# led3.net
KiCad netlist of a schematic drawn in Altium Designer
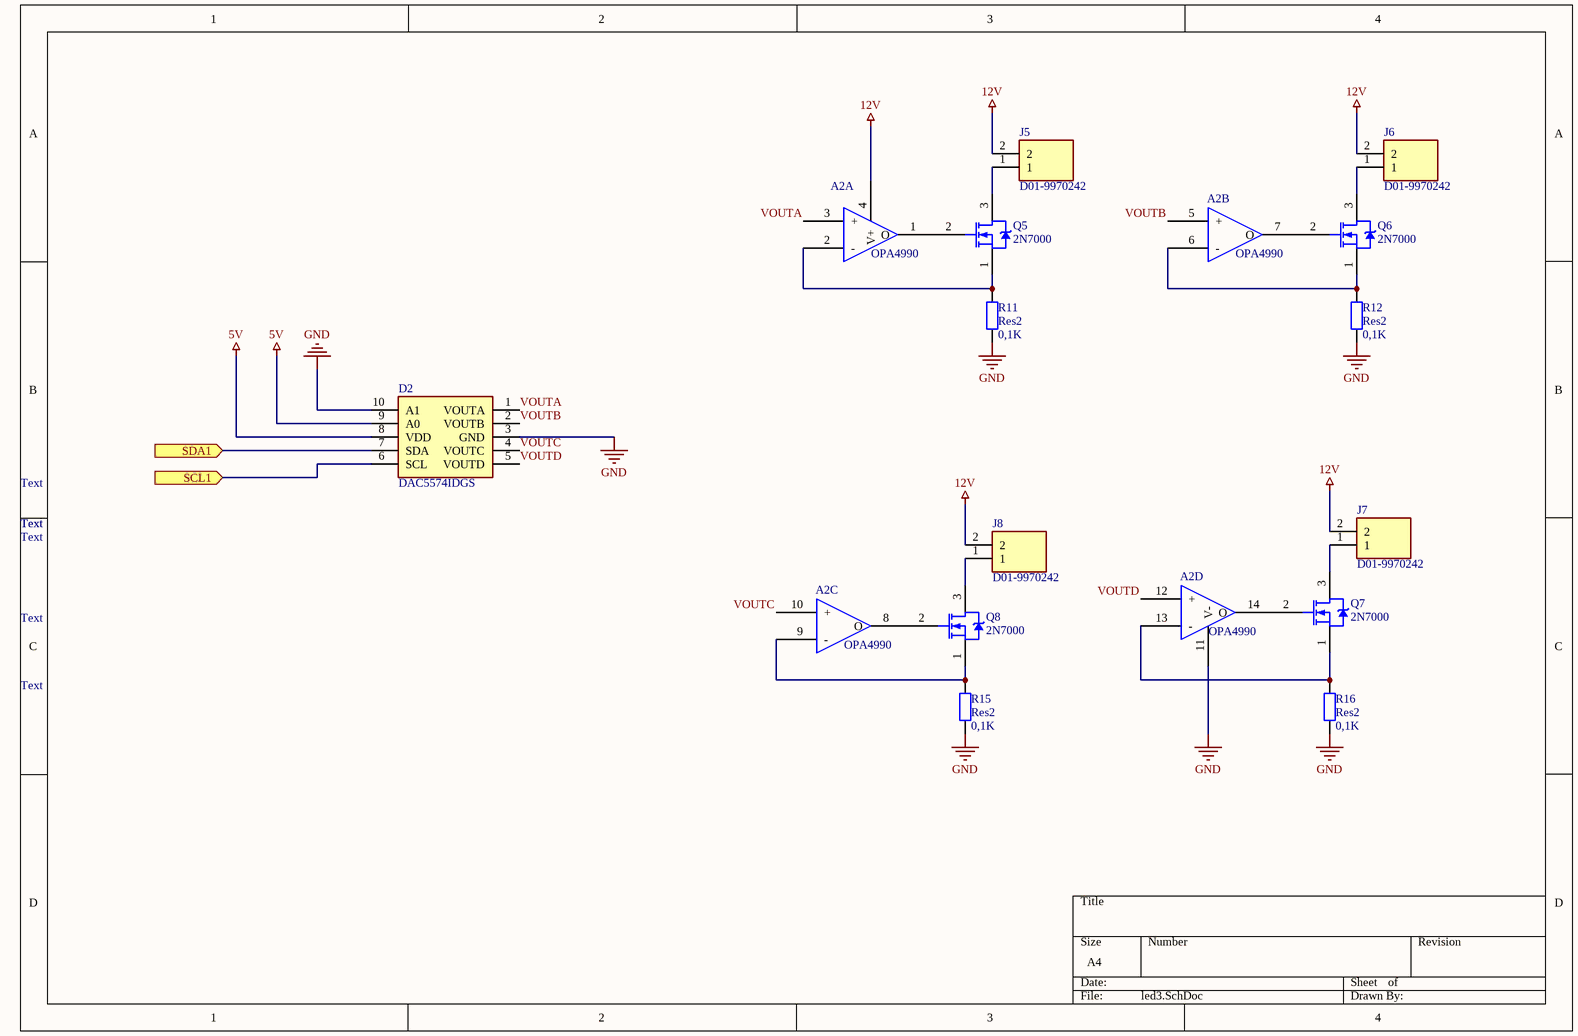
[diagram p0: led3.SchDoc]

(export (version "E")
  (design (tool "Eeschema 10.0.6"))
  (components
    (comp (ref "A2")
      (value "OPA4990")
      (footprint "SOIC127P600X175-14N")
      (libsource (lib "Kalibracija") (part "OPA4990"))
    )
    (comp (ref "D2")
      (value "DAC5574IDGS")
      (footprint "SOP50P490X110-10N")
      (description "Integrated Circuit")
      (fields
        (field (name "MOUSER PART NUMBER") "595-DAC5574IDGS")
        (field (name "RS PART NUMBER") "6621533P")
      )
      (libsource (lib "*") (part "DAC5574IDGS"))
    )
    (comp (ref "J5")
      (value "D01-9970242")
      (footprint "HDR1X2")
      (description "Connector")
      (fields (field (name "MOUSER PART NUMBER") "855-D01-9970242"))
      (libsource (lib "SamacSys2") (part "D01-9970242"))
    )
    (comp (ref "J6")
      (value "D01-9970242")
      (footprint "HDR1X2")
      (description "Connector")
      (fields (field (name "MOUSER PART NUMBER") "855-D01-9970242"))
      (libsource (lib "SamacSys2") (part "D01-9970242"))
    )
    (comp (ref "J7")
      (value "D01-9970242")
      (footprint "HDR1X2")
      (description "Connector")
      (fields (field (name "MOUSER PART NUMBER") "855-D01-9970242"))
      (libsource (lib "SamacSys2") (part "D01-9970242"))
    )
    (comp (ref "J8")
      (value "D01-9970242")
      (footprint "HDR1X2")
      (description "Connector")
      (fields (field (name "MOUSER PART NUMBER") "855-D01-9970242"))
      (libsource (lib "SamacSys2") (part "D01-9970242"))
    )
    (comp (ref "Q5")
      (value "2N7000")
      (footprint "ONSC-TO-92-3-29-11")
      (description "Small Signal MOSFET, 200 mA, 60 V, N-Channel, 3-Pin TO-92, Bulk Box")
      (fields (field (name "MANUFACTURER") "On Semiconductor"))
      (libsource (lib "Components - 24.04.20 - 07.58") (part "CMP-1058-00936-1"))
    )
    (comp (ref "Q6")
      (value "2N7000")
      (footprint "ONSC-TO-92-3-29-11")
      (description "Small Signal MOSFET, 200 mA, 60 V, N-Channel, 3-Pin TO-92, Bulk Box")
      (fields (field (name "MANUFACTURER") "On Semiconductor"))
      (libsource (lib "Components - 24.04.20 - 07.58") (part "CMP-1058-00936-1"))
    )
    (comp (ref "Q7")
      (value "2N7000")
      (footprint "ONSC-TO-92-3-29-11")
      (description "Small Signal MOSFET, 200 mA, 60 V, N-Channel, 3-Pin TO-92, Bulk Box")
      (fields (field (name "MANUFACTURER") "On Semiconductor"))
      (libsource (lib "Components - 24.04.20 - 07.58") (part "CMP-1058-00936-1"))
    )
    (comp (ref "Q8")
      (value "2N7000")
      (footprint "ONSC-TO-92-3-29-11")
      (description "Small Signal MOSFET, 200 mA, 60 V, N-Channel, 3-Pin TO-92, Bulk Box")
      (fields (field (name "MANUFACTURER") "On Semiconductor"))
      (libsource (lib "Components - 24.04.20 - 07.58") (part "CMP-1058-00936-1"))
    )
    (comp (ref "R11")
      (value "Res2")
      (footprint "C1210")
      (description "Resistor")
      (fields (field (name "ALTIUM_VALUE") "0,1K") (field (name "PUBLISHER") "Altium Limited"))
      (libsource (lib "Miscellaneous Devices") (part "Res2"))
    )
    (comp (ref "R12")
      (value "Res2")
      (footprint "C1210")
      (description "Resistor")
      (fields (field (name "ALTIUM_VALUE") "0,1K") (field (name "PUBLISHER") "Altium Limited"))
      (libsource (lib "Miscellaneous Devices") (part "Res2"))
    )
    (comp (ref "R15")
      (value "Res2")
      (footprint "C1210")
      (description "Resistor")
      (fields (field (name "ALTIUM_VALUE") "0,1K") (field (name "PUBLISHER") "Altium Limited"))
      (libsource (lib "Miscellaneous Devices") (part "Res2"))
    )
    (comp (ref "R16")
      (value "Res2")
      (footprint "C1210")
      (description "Resistor")
      (fields (field (name "ALTIUM_VALUE") "0,1K") (field (name "PUBLISHER") "Altium Limited"))
      (libsource (lib "Miscellaneous Devices") (part "Res2"))
    )
  )
  (nets
    (net (code "1") (name "/SCL1") (class "Default")
      (node (ref "D2") (pin "6") (pinfunction "SCL_6") (pintype "passive"))
    )
    (net (code "2") (name "/SDA1") (class "Default")
      (node (ref "D2") (pin "7") (pinfunction "SDA_7") (pintype "passive"))
    )
    (net (code "3") (name "/VOUTA") (class "Default")
      (node (ref "A2") (pin "3") (pinfunction "+_3") (pintype "passive"))
      (node (ref "D2") (pin "1") (pinfunction "VOUTA_1") (pintype "passive"))
    )
    (net (code "4") (name "/VOUTB") (class "Default")
      (node (ref "A2") (pin "5") (pinfunction "+_5") (pintype "passive"))
      (node (ref "D2") (pin "2") (pinfunction "VOUTB_2") (pintype "passive"))
    )
    (net (code "5") (name "/VOUTC") (class "Default")
      (node (ref "A2") (pin "10") (pinfunction "+_10") (pintype "passive"))
      (node (ref "D2") (pin "4") (pinfunction "VOUTC_4") (pintype "passive"))
    )
    (net (code "6") (name "/VOUTD") (class "Default")
      (node (ref "A2") (pin "12") (pinfunction "+_12") (pintype "passive"))
      (node (ref "D2") (pin "5") (pinfunction "VOUTD_5") (pintype "passive"))
    )
    (net (code "7") (name "5V") (class "Default")
      (node (ref "D2") (pin "8") (pinfunction "VDD_8") (pintype "passive"))
      (node (ref "D2") (pin "9") (pinfunction "A0_9") (pintype "passive"))
    )
    (net (code "8") (name "12V") (class "Default")
      (node (ref "A2") (pin "4") (pinfunction "V+_4") (pintype "power_in"))
      (node (ref "J5") (pin "2") (pinfunction "2_2") (pintype "passive"))
      (node (ref "J6") (pin "2") (pinfunction "2_2") (pintype "passive"))
      (node (ref "J7") (pin "2") (pinfunction "2_2") (pintype "passive"))
      (node (ref "J8") (pin "2") (pinfunction "2_2") (pintype "passive"))
    )
    (net (code "9") (name "GND") (class "Default")
      (node (ref "A2") (pin "11") (pinfunction "V-_11") (pintype "power_in"))
      (node (ref "D2") (pin "10") (pinfunction "A1_10") (pintype "passive"))
      (node (ref "D2") (pin "3") (pinfunction "GND_3") (pintype "passive"))
      (node (ref "R11") (pin "1") (pinfunction "1_1") (pintype "passive"))
      (node (ref "R12") (pin "1") (pinfunction "1_1") (pintype "passive"))
      (node (ref "R15") (pin "1") (pinfunction "1_1") (pintype "passive"))
      (node (ref "R16") (pin "1") (pinfunction "1_1") (pintype "passive"))
    )
    (net (code "10") (name "Net-(A2A--)") (class "Default")
      (node (ref "A2") (pin "2") (pinfunction "-_2") (pintype "passive"))
      (node (ref "Q5") (pin "1") (pinfunction "S_1") (pintype "passive"))
      (node (ref "R11") (pin "2") (pinfunction "2_2") (pintype "passive"))
    )
    (net (code "11") (name "Net-(A2A-O)") (class "Default")
      (node (ref "A2") (pin "1") (pinfunction "O_1") (pintype "passive"))
      (node (ref "Q5") (pin "2") (pinfunction "G_2") (pintype "passive"))
    )
    (net (code "12") (name "Net-(A2B--)") (class "Default")
      (node (ref "A2") (pin "6") (pinfunction "-_6") (pintype "passive"))
      (node (ref "Q6") (pin "1") (pinfunction "S_1") (pintype "passive"))
      (node (ref "R12") (pin "2") (pinfunction "2_2") (pintype "passive"))
    )
    (net (code "13") (name "Net-(A2B-O)") (class "Default")
      (node (ref "A2") (pin "7") (pinfunction "O_7") (pintype "passive"))
      (node (ref "Q6") (pin "2") (pinfunction "G_2") (pintype "passive"))
    )
    (net (code "14") (name "Net-(A2C--)") (class "Default")
      (node (ref "A2") (pin "9") (pinfunction "-_9") (pintype "passive"))
      (node (ref "Q8") (pin "1") (pinfunction "S_1") (pintype "passive"))
      (node (ref "R15") (pin "2") (pinfunction "2_2") (pintype "passive"))
    )
    (net (code "15") (name "Net-(A2C-O)") (class "Default")
      (node (ref "A2") (pin "8") (pinfunction "O_8") (pintype "passive"))
      (node (ref "Q8") (pin "2") (pinfunction "G_2") (pintype "passive"))
    )
    (net (code "16") (name "Net-(A2D--)") (class "Default")
      (node (ref "A2") (pin "13") (pinfunction "-_13") (pintype "passive"))
      (node (ref "Q7") (pin "1") (pinfunction "S_1") (pintype "passive"))
      (node (ref "R16") (pin "2") (pinfunction "2_2") (pintype "passive"))
    )
    (net (code "17") (name "Net-(A2D-O)") (class "Default")
      (node (ref "A2") (pin "14") (pinfunction "O_14") (pintype "passive"))
      (node (ref "Q7") (pin "2") (pinfunction "G_2") (pintype "passive"))
    )
    (net (code "18") (name "Net-(Q5-D)") (class "Default")
      (node (ref "J5") (pin "1") (pinfunction "1_1") (pintype "passive"))
      (node (ref "Q5") (pin "3") (pinfunction "D_3") (pintype "passive"))
    )
    (net (code "19") (name "Net-(Q6-D)") (class "Default")
      (node (ref "J6") (pin "1") (pinfunction "1_1") (pintype "passive"))
      (node (ref "Q6") (pin "3") (pinfunction "D_3") (pintype "passive"))
    )
    (net (code "20") (name "Net-(Q7-D)") (class "Default")
      (node (ref "J7") (pin "1") (pinfunction "1_1") (pintype "passive"))
      (node (ref "Q7") (pin "3") (pinfunction "D_3") (pintype "passive"))
    )
    (net (code "21") (name "Net-(Q8-D)") (class "Default")
      (node (ref "J8") (pin "1") (pinfunction "1_1") (pintype "passive"))
      (node (ref "Q8") (pin "3") (pinfunction "D_3") (pintype "passive"))
    )
  )
)
